# Sheet4.net
KiCad netlist of a schematic drawn in Altium Designer
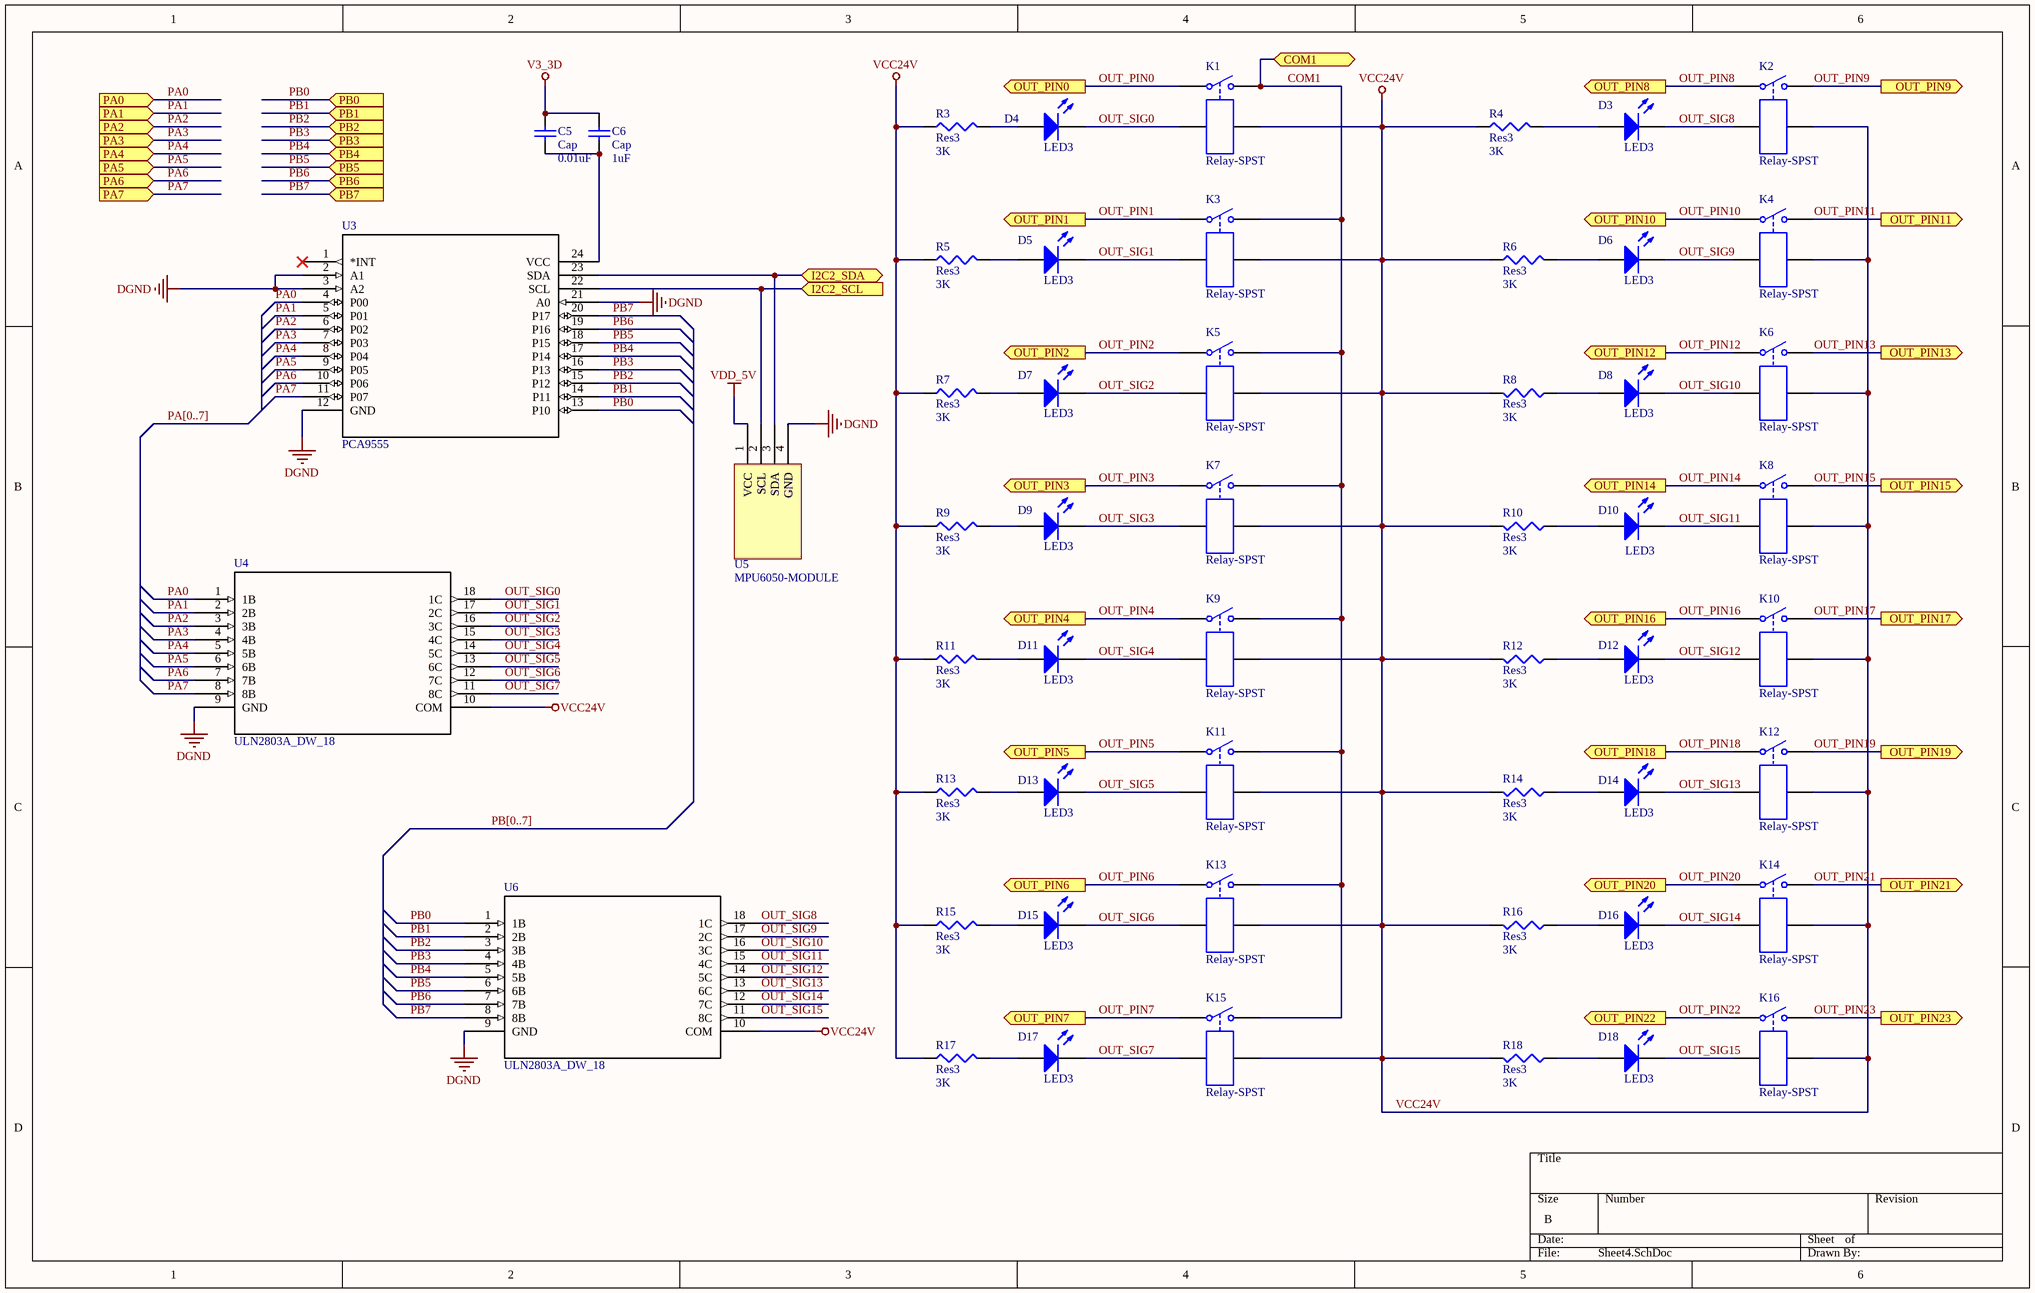
[diagram p0: Sheet4.SchDoc]

(export (version "E")
  (design (tool "Eeschema 10.0.6"))
  (components
    (comp (ref "C5")
      (value "Cap")
      (footprint "0805_cap")
      (description "Capacitor")
      (fields (field (name "ALTIUM_VALUE") "0.01uF") (field (name "PUBLISHER") "Altium Limited"))
      (libsource (lib "Miscellaneous Devices") (part "Cap"))
    )
    (comp (ref "C6")
      (value "Cap")
      (footprint "0805_cap")
      (description "Capacitor")
      (fields (field (name "ALTIUM_VALUE") "1uF") (field (name "PUBLISHER") "Altium Limited"))
      (libsource (lib "Miscellaneous Devices") (part "Cap"))
    )
    (comp (ref "D3")
      (value "LED3")
      (footprint "0805LED")
      (description "Typical BLUE SiC LED")
      (fields (field (name "PUBLISHER") "Altium Limited"))
      (libsource (lib "Miscellaneous Devices") (part "LED3"))
    )
    (comp (ref "D4")
      (value "LED3")
      (footprint "0805LED")
      (description "Typical BLUE SiC LED")
      (fields (field (name "PUBLISHER") "Altium Limited"))
      (libsource (lib "Miscellaneous Devices") (part "LED3"))
    )
    (comp (ref "D5")
      (value "LED3")
      (footprint "0805LED")
      (description "Typical BLUE SiC LED")
      (fields (field (name "PUBLISHER") "Altium Limited"))
      (libsource (lib "Miscellaneous Devices") (part "LED3"))
    )
    (comp (ref "D6")
      (value "LED3")
      (footprint "0805LED")
      (description "Typical BLUE SiC LED")
      (fields (field (name "PUBLISHER") "Altium Limited"))
      (libsource (lib "Miscellaneous Devices") (part "LED3"))
    )
    (comp (ref "D7")
      (value "LED3")
      (footprint "0805LED")
      (description "Typical BLUE SiC LED")
      (fields (field (name "PUBLISHER") "Altium Limited"))
      (libsource (lib "Miscellaneous Devices") (part "LED3"))
    )
    (comp (ref "D8")
      (value "LED3")
      (footprint "0805LED")
      (description "Typical BLUE SiC LED")
      (fields (field (name "PUBLISHER") "Altium Limited"))
      (libsource (lib "Miscellaneous Devices") (part "LED3"))
    )
    (comp (ref "D9")
      (value "LED3")
      (footprint "0805LED")
      (description "Typical BLUE SiC LED")
      (fields (field (name "PUBLISHER") "Altium Limited"))
      (libsource (lib "Miscellaneous Devices") (part "LED3"))
    )
    (comp (ref "D10")
      (value "LED3")
      (footprint "0805LED")
      (description "Typical BLUE SiC LED")
      (fields (field (name "PUBLISHER") "Altium Limited"))
      (libsource (lib "Miscellaneous Devices") (part "LED3"))
    )
    (comp (ref "D11")
      (value "LED3")
      (footprint "0805LED")
      (description "Typical BLUE SiC LED")
      (fields (field (name "PUBLISHER") "Altium Limited"))
      (libsource (lib "Miscellaneous Devices") (part "LED3"))
    )
    (comp (ref "D12")
      (value "LED3")
      (footprint "0805LED")
      (description "Typical BLUE SiC LED")
      (fields (field (name "PUBLISHER") "Altium Limited"))
      (libsource (lib "Miscellaneous Devices") (part "LED3"))
    )
    (comp (ref "D13")
      (value "LED3")
      (footprint "0805LED")
      (description "Typical BLUE SiC LED")
      (fields (field (name "PUBLISHER") "Altium Limited"))
      (libsource (lib "Miscellaneous Devices") (part "LED3"))
    )
    (comp (ref "D14")
      (value "LED3")
      (footprint "0805LED")
      (description "Typical BLUE SiC LED")
      (fields (field (name "PUBLISHER") "Altium Limited"))
      (libsource (lib "Miscellaneous Devices") (part "LED3"))
    )
    (comp (ref "D15")
      (value "LED3")
      (footprint "0805LED")
      (description "Typical BLUE SiC LED")
      (fields (field (name "PUBLISHER") "Altium Limited"))
      (libsource (lib "Miscellaneous Devices") (part "LED3"))
    )
    (comp (ref "D16")
      (value "LED3")
      (footprint "0805LED")
      (description "Typical BLUE SiC LED")
      (fields (field (name "PUBLISHER") "Altium Limited"))
      (libsource (lib "Miscellaneous Devices") (part "LED3"))
    )
    (comp (ref "D17")
      (value "LED3")
      (footprint "0805LED")
      (description "Typical BLUE SiC LED")
      (fields (field (name "PUBLISHER") "Altium Limited"))
      (libsource (lib "Miscellaneous Devices") (part "LED3"))
    )
    (comp (ref "D18")
      (value "LED3")
      (footprint "0805LED")
      (description "Typical BLUE SiC LED")
      (fields (field (name "PUBLISHER") "Altium Limited"))
      (libsource (lib "Miscellaneous Devices") (part "LED3"))
    )
    (comp (ref "K1")
      (value "Relay-SPST")
      (footprint "PA1a-24v")
      (description "Single-Pole Single-Throw Relay")
      (fields (field (name "PUBLISHER") "Altium Limited"))
      (libsource (lib "Miscellaneous Devices") (part "Relay-SPST"))
    )
    (comp (ref "K2")
      (value "Relay-SPST")
      (footprint "PA1a-24v")
      (description "Single-Pole Single-Throw Relay")
      (fields (field (name "PUBLISHER") "Altium Limited"))
      (libsource (lib "Miscellaneous Devices") (part "Relay-SPST"))
    )
    (comp (ref "K3")
      (value "Relay-SPST")
      (footprint "PA1a-24v")
      (description "Single-Pole Single-Throw Relay")
      (fields (field (name "PUBLISHER") "Altium Limited"))
      (libsource (lib "Miscellaneous Devices") (part "Relay-SPST"))
    )
    (comp (ref "K4")
      (value "Relay-SPST")
      (footprint "PA1a-24v")
      (description "Single-Pole Single-Throw Relay")
      (fields (field (name "PUBLISHER") "Altium Limited"))
      (libsource (lib "Miscellaneous Devices") (part "Relay-SPST"))
    )
    (comp (ref "K5")
      (value "Relay-SPST")
      (footprint "PA1a-24v")
      (description "Single-Pole Single-Throw Relay")
      (fields (field (name "PUBLISHER") "Altium Limited"))
      (libsource (lib "Miscellaneous Devices") (part "Relay-SPST"))
    )
    (comp (ref "K6")
      (value "Relay-SPST")
      (footprint "PA1a-24v")
      (description "Single-Pole Single-Throw Relay")
      (fields (field (name "PUBLISHER") "Altium Limited"))
      (libsource (lib "Miscellaneous Devices") (part "Relay-SPST"))
    )
    (comp (ref "K7")
      (value "Relay-SPST")
      (footprint "PA1a-24v")
      (description "Single-Pole Single-Throw Relay")
      (fields (field (name "PUBLISHER") "Altium Limited"))
      (libsource (lib "Miscellaneous Devices") (part "Relay-SPST"))
    )
    (comp (ref "K8")
      (value "Relay-SPST")
      (footprint "PA1a-24v")
      (description "Single-Pole Single-Throw Relay")
      (fields (field (name "PUBLISHER") "Altium Limited"))
      (libsource (lib "Miscellaneous Devices") (part "Relay-SPST"))
    )
    (comp (ref "K9")
      (value "Relay-SPST")
      (footprint "PA1a-24v")
      (description "Single-Pole Single-Throw Relay")
      (fields (field (name "PUBLISHER") "Altium Limited"))
      (libsource (lib "Miscellaneous Devices") (part "Relay-SPST"))
    )
    (comp (ref "K10")
      (value "Relay-SPST")
      (footprint "PA1a-24v")
      (description "Single-Pole Single-Throw Relay")
      (fields (field (name "PUBLISHER") "Altium Limited"))
      (libsource (lib "Miscellaneous Devices") (part "Relay-SPST"))
    )
    (comp (ref "K11")
      (value "Relay-SPST")
      (footprint "PA1a-24v")
      (description "Single-Pole Single-Throw Relay")
      (fields (field (name "PUBLISHER") "Altium Limited"))
      (libsource (lib "Miscellaneous Devices") (part "Relay-SPST"))
    )
    (comp (ref "K12")
      (value "Relay-SPST")
      (footprint "PA1a-24v")
      (description "Single-Pole Single-Throw Relay")
      (fields (field (name "PUBLISHER") "Altium Limited"))
      (libsource (lib "Miscellaneous Devices") (part "Relay-SPST"))
    )
    (comp (ref "K13")
      (value "Relay-SPST")
      (footprint "PA1a-24v")
      (description "Single-Pole Single-Throw Relay")
      (fields (field (name "PUBLISHER") "Altium Limited"))
      (libsource (lib "Miscellaneous Devices") (part "Relay-SPST"))
    )
    (comp (ref "K14")
      (value "Relay-SPST")
      (footprint "PA1a-24v")
      (description "Single-Pole Single-Throw Relay")
      (fields (field (name "PUBLISHER") "Altium Limited"))
      (libsource (lib "Miscellaneous Devices") (part "Relay-SPST"))
    )
    (comp (ref "K15")
      (value "Relay-SPST")
      (footprint "PA1a-24v")
      (description "Single-Pole Single-Throw Relay")
      (fields (field (name "PUBLISHER") "Altium Limited"))
      (libsource (lib "Miscellaneous Devices") (part "Relay-SPST"))
    )
    (comp (ref "K16")
      (value "Relay-SPST")
      (footprint "PA1a-24v")
      (description "Single-Pole Single-Throw Relay")
      (fields (field (name "PUBLISHER") "Altium Limited"))
      (libsource (lib "Miscellaneous Devices") (part "Relay-SPST"))
    )
    (comp (ref "R3")
      (value "Res3")
      (footprint "0805")
      (description "Resistor")
      (fields (field (name "ALTIUM_VALUE") "3K") (field (name "PUBLISHER") "Altium Limited"))
      (libsource (lib "Miscellaneous Devices") (part "Res3"))
    )
    (comp (ref "R4")
      (value "Res3")
      (footprint "0805")
      (description "Resistor")
      (fields (field (name "ALTIUM_VALUE") "3K") (field (name "PUBLISHER") "Altium Limited"))
      (libsource (lib "Miscellaneous Devices") (part "Res3"))
    )
    (comp (ref "R5")
      (value "Res3")
      (footprint "0805")
      (description "Resistor")
      (fields (field (name "ALTIUM_VALUE") "3K") (field (name "PUBLISHER") "Altium Limited"))
      (libsource (lib "Miscellaneous Devices") (part "Res3"))
    )
    (comp (ref "R6")
      (value "Res3")
      (footprint "0805")
      (description "Resistor")
      (fields (field (name "ALTIUM_VALUE") "3K") (field (name "PUBLISHER") "Altium Limited"))
      (libsource (lib "Miscellaneous Devices") (part "Res3"))
    )
    (comp (ref "R7")
      (value "Res3")
      (footprint "0805")
      (description "Resistor")
      (fields (field (name "ALTIUM_VALUE") "3K") (field (name "PUBLISHER") "Altium Limited"))
      (libsource (lib "Miscellaneous Devices") (part "Res3"))
    )
    (comp (ref "R8")
      (value "Res3")
      (footprint "0805")
      (description "Resistor")
      (fields (field (name "ALTIUM_VALUE") "3K") (field (name "PUBLISHER") "Altium Limited"))
      (libsource (lib "Miscellaneous Devices") (part "Res3"))
    )
    (comp (ref "R9")
      (value "Res3")
      (footprint "0805")
      (description "Resistor")
      (fields (field (name "ALTIUM_VALUE") "3K") (field (name "PUBLISHER") "Altium Limited"))
      (libsource (lib "Miscellaneous Devices") (part "Res3"))
    )
    (comp (ref "R10")
      (value "Res3")
      (footprint "0805")
      (description "Resistor")
      (fields (field (name "ALTIUM_VALUE") "3K") (field (name "PUBLISHER") "Altium Limited"))
      (libsource (lib "Miscellaneous Devices") (part "Res3"))
    )
    (comp (ref "R11")
      (value "Res3")
      (footprint "0805")
      (description "Resistor")
      (fields (field (name "ALTIUM_VALUE") "3K") (field (name "PUBLISHER") "Altium Limited"))
      (libsource (lib "Miscellaneous Devices") (part "Res3"))
    )
    (comp (ref "R12")
      (value "Res3")
      (footprint "0805")
      (description "Resistor")
      (fields (field (name "ALTIUM_VALUE") "3K") (field (name "PUBLISHER") "Altium Limited"))
      (libsource (lib "Miscellaneous Devices") (part "Res3"))
    )
    (comp (ref "R13")
      (value "Res3")
      (footprint "0805")
      (description "Resistor")
      (fields (field (name "ALTIUM_VALUE") "3K") (field (name "PUBLISHER") "Altium Limited"))
      (libsource (lib "Miscellaneous Devices") (part "Res3"))
    )
    (comp (ref "R14")
      (value "Res3")
      (footprint "0805")
      (description "Resistor")
      (fields (field (name "ALTIUM_VALUE") "3K") (field (name "PUBLISHER") "Altium Limited"))
      (libsource (lib "Miscellaneous Devices") (part "Res3"))
    )
    (comp (ref "R15")
      (value "Res3")
      (footprint "0805")
      (description "Resistor")
      (fields (field (name "ALTIUM_VALUE") "3K") (field (name "PUBLISHER") "Altium Limited"))
      (libsource (lib "Miscellaneous Devices") (part "Res3"))
    )
    (comp (ref "R16")
      (value "Res3")
      (footprint "0805")
      (description "Resistor")
      (fields (field (name "ALTIUM_VALUE") "3K") (field (name "PUBLISHER") "Altium Limited"))
      (libsource (lib "Miscellaneous Devices") (part "Res3"))
    )
    (comp (ref "R17")
      (value "Res3")
      (footprint "0805")
      (description "Resistor")
      (fields (field (name "ALTIUM_VALUE") "3K") (field (name "PUBLISHER") "Altium Limited"))
      (libsource (lib "Miscellaneous Devices") (part "Res3"))
    )
    (comp (ref "R18")
      (value "Res3")
      (footprint "0805")
      (description "Resistor")
      (fields (field (name "ALTIUM_VALUE") "3K") (field (name "PUBLISHER") "Altium Limited"))
      (libsource (lib "Miscellaneous Devices") (part "Res3"))
    )
    (comp (ref "U3")
      (value "PCA9555")
      (footprint "PW24")
      (description "Imported")
      (fields
        (field (name "MANUFACTURER") "Texas Instruments")
        (field (name "GENERIC_PART_NUMBER") "PCF8575")
      )
      (libsource (lib "dolphi_ecs") (part "PCF8575_PW_24"))
    )
    (comp (ref "U4")
      (value "ULN2803A_DW_18")
      (footprint "DW18")
      (description "Imported")
      (fields
        (field (name "MANUFACTURER") "Texas Instruments")
        (field (name "GENERIC_PART_NUMBER") "ULN2803A")
      )
      (libsource (lib "dolphi_ecs") (part "ULN2803A_DW_18"))
    )
    (comp (ref "U5")
      (value "MPU6050-MODULE")
      (footprint "MPU6050-MODULE")
      (libsource (lib "dolphi_ecs") (part "MPU6050-MODULE"))
    )
    (comp (ref "U6")
      (value "ULN2803A_DW_18")
      (footprint "DW18")
      (description "Imported")
      (fields
        (field (name "MANUFACTURER") "Texas Instruments")
        (field (name "GENERIC_PART_NUMBER") "ULN2803A")
      )
      (libsource (lib "dolphi_ecs") (part "ULN2803A_DW_18"))
    )
  )
  (nets
    (net (code "1") (name "/COM1") (class "Default")
      (node (ref "K1") (pin "2") (pinfunction "2_2") (pintype "passive"))
      (node (ref "K11") (pin "2") (pinfunction "2_2") (pintype "passive"))
      (node (ref "K13") (pin "2") (pinfunction "2_2") (pintype "passive"))
      (node (ref "K15") (pin "2") (pinfunction "2_2") (pintype "passive"))
      (node (ref "K3") (pin "2") (pinfunction "2_2") (pintype "passive"))
      (node (ref "K5") (pin "2") (pinfunction "2_2") (pintype "passive"))
      (node (ref "K7") (pin "2") (pinfunction "2_2") (pintype "passive"))
      (node (ref "K9") (pin "2") (pinfunction "2_2") (pintype "passive"))
    )
    (net (code "2") (name "/I2C2_SCL") (class "Default")
      (node (ref "U3") (pin "22") (pinfunction "SCL_22") (pintype "passive"))
      (node (ref "U5") (pin "2") (pinfunction "SCL_2") (pintype "passive"))
    )
    (net (code "3") (name "/I2C2_SDA") (class "Default")
      (node (ref "U3") (pin "23") (pinfunction "SDA_23") (pintype "passive"))
      (node (ref "U5") (pin "3") (pinfunction "SDA_3") (pintype "passive"))
    )
    (net (code "4") (name "/OUT_PIN0") (class "Default")
      (node (ref "K1") (pin "1") (pinfunction "1_1") (pintype "passive"))
    )
    (net (code "5") (name "/OUT_PIN1") (class "Default")
      (node (ref "K3") (pin "1") (pinfunction "1_1") (pintype "passive"))
    )
    (net (code "6") (name "/OUT_PIN2") (class "Default")
      (node (ref "K5") (pin "1") (pinfunction "1_1") (pintype "passive"))
    )
    (net (code "7") (name "/OUT_PIN3") (class "Default")
      (node (ref "K7") (pin "1") (pinfunction "1_1") (pintype "passive"))
    )
    (net (code "8") (name "/OUT_PIN4") (class "Default")
      (node (ref "K9") (pin "1") (pinfunction "1_1") (pintype "passive"))
    )
    (net (code "9") (name "/OUT_PIN5") (class "Default")
      (node (ref "K11") (pin "1") (pinfunction "1_1") (pintype "passive"))
    )
    (net (code "10") (name "/OUT_PIN6") (class "Default")
      (node (ref "K13") (pin "1") (pinfunction "1_1") (pintype "passive"))
    )
    (net (code "11") (name "/OUT_PIN7") (class "Default")
      (node (ref "K15") (pin "1") (pinfunction "1_1") (pintype "passive"))
    )
    (net (code "12") (name "/OUT_PIN8") (class "Default")
      (node (ref "K2") (pin "1") (pinfunction "1_1") (pintype "passive"))
    )
    (net (code "13") (name "/OUT_PIN9") (class "Default")
      (node (ref "K2") (pin "2") (pinfunction "2_2") (pintype "passive"))
    )
    (net (code "14") (name "/OUT_PIN10") (class "Default")
      (node (ref "K4") (pin "1") (pinfunction "1_1") (pintype "passive"))
    )
    (net (code "15") (name "/OUT_PIN11") (class "Default")
      (node (ref "K4") (pin "2") (pinfunction "2_2") (pintype "passive"))
    )
    (net (code "16") (name "/OUT_PIN12") (class "Default")
      (node (ref "K6") (pin "1") (pinfunction "1_1") (pintype "passive"))
    )
    (net (code "17") (name "/OUT_PIN13") (class "Default")
      (node (ref "K6") (pin "2") (pinfunction "2_2") (pintype "passive"))
    )
    (net (code "18") (name "/OUT_PIN14") (class "Default")
      (node (ref "K8") (pin "1") (pinfunction "1_1") (pintype "passive"))
    )
    (net (code "19") (name "/OUT_PIN15") (class "Default")
      (node (ref "K8") (pin "2") (pinfunction "2_2") (pintype "passive"))
    )
    (net (code "20") (name "/OUT_PIN16") (class "Default")
      (node (ref "K10") (pin "1") (pinfunction "1_1") (pintype "passive"))
    )
    (net (code "21") (name "/OUT_PIN17") (class "Default")
      (node (ref "K10") (pin "2") (pinfunction "2_2") (pintype "passive"))
    )
    (net (code "22") (name "/OUT_PIN18") (class "Default")
      (node (ref "K12") (pin "1") (pinfunction "1_1") (pintype "passive"))
    )
    (net (code "23") (name "/OUT_PIN19") (class "Default")
      (node (ref "K12") (pin "2") (pinfunction "2_2") (pintype "passive"))
    )
    (net (code "24") (name "/OUT_PIN20") (class "Default")
      (node (ref "K14") (pin "1") (pinfunction "1_1") (pintype "passive"))
    )
    (net (code "25") (name "/OUT_PIN21") (class "Default")
      (node (ref "K14") (pin "2") (pinfunction "2_2") (pintype "passive"))
    )
    (net (code "26") (name "/OUT_PIN22") (class "Default")
      (node (ref "K16") (pin "1") (pinfunction "1_1") (pintype "passive"))
    )
    (net (code "27") (name "/OUT_PIN23") (class "Default")
      (node (ref "K16") (pin "2") (pinfunction "2_2") (pintype "passive"))
    )
    (net (code "28") (name "/OUT_SIG0") (class "Default")
      (node (ref "D4") (pin "2") (pinfunction "K_2") (pintype "passive"))
      (node (ref "K1") (pin "3") (pinfunction "3_3") (pintype "passive"))
      (node (ref "U4") (pin "18") (pinfunction "1C_18") (pintype "output"))
    )
    (net (code "29") (name "/OUT_SIG1") (class "Default")
      (node (ref "D5") (pin "2") (pinfunction "K_2") (pintype "passive"))
      (node (ref "K3") (pin "3") (pinfunction "3_3") (pintype "passive"))
      (node (ref "U4") (pin "17") (pinfunction "2C_17") (pintype "output"))
    )
    (net (code "30") (name "/OUT_SIG2") (class "Default")
      (node (ref "D7") (pin "2") (pinfunction "K_2") (pintype "passive"))
      (node (ref "K5") (pin "3") (pinfunction "3_3") (pintype "passive"))
      (node (ref "U4") (pin "16") (pinfunction "3C_16") (pintype "output"))
    )
    (net (code "31") (name "/OUT_SIG3") (class "Default")
      (node (ref "D9") (pin "2") (pinfunction "K_2") (pintype "passive"))
      (node (ref "K7") (pin "3") (pinfunction "3_3") (pintype "passive"))
      (node (ref "U4") (pin "15") (pinfunction "4C_15") (pintype "output"))
    )
    (net (code "32") (name "/OUT_SIG4") (class "Default")
      (node (ref "D11") (pin "2") (pinfunction "K_2") (pintype "passive"))
      (node (ref "K9") (pin "3") (pinfunction "3_3") (pintype "passive"))
      (node (ref "U4") (pin "14") (pinfunction "5C_14") (pintype "output"))
    )
    (net (code "33") (name "/OUT_SIG5") (class "Default")
      (node (ref "D13") (pin "2") (pinfunction "K_2") (pintype "passive"))
      (node (ref "K11") (pin "3") (pinfunction "3_3") (pintype "passive"))
      (node (ref "U4") (pin "13") (pinfunction "6C_13") (pintype "output"))
    )
    (net (code "34") (name "/OUT_SIG6") (class "Default")
      (node (ref "D15") (pin "2") (pinfunction "K_2") (pintype "passive"))
      (node (ref "K13") (pin "3") (pinfunction "3_3") (pintype "passive"))
      (node (ref "U4") (pin "12") (pinfunction "7C_12") (pintype "output"))
    )
    (net (code "35") (name "/OUT_SIG7") (class "Default")
      (node (ref "D17") (pin "2") (pinfunction "K_2") (pintype "passive"))
      (node (ref "K15") (pin "3") (pinfunction "3_3") (pintype "passive"))
      (node (ref "U4") (pin "11") (pinfunction "8C_11") (pintype "output"))
    )
    (net (code "36") (name "/OUT_SIG8") (class "Default")
      (node (ref "D3") (pin "2") (pinfunction "K_2") (pintype "passive"))
      (node (ref "K2") (pin "3") (pinfunction "3_3") (pintype "passive"))
      (node (ref "U6") (pin "18") (pinfunction "1C_18") (pintype "output"))
    )
    (net (code "37") (name "/OUT_SIG9") (class "Default")
      (node (ref "D6") (pin "2") (pinfunction "K_2") (pintype "passive"))
      (node (ref "K4") (pin "3") (pinfunction "3_3") (pintype "passive"))
      (node (ref "U6") (pin "17") (pinfunction "2C_17") (pintype "output"))
    )
    (net (code "38") (name "/OUT_SIG10") (class "Default")
      (node (ref "D8") (pin "2") (pinfunction "K_2") (pintype "passive"))
      (node (ref "K6") (pin "3") (pinfunction "3_3") (pintype "passive"))
      (node (ref "U6") (pin "16") (pinfunction "3C_16") (pintype "output"))
    )
    (net (code "39") (name "/OUT_SIG11") (class "Default")
      (node (ref "D10") (pin "2") (pinfunction "K_2") (pintype "passive"))
      (node (ref "K8") (pin "3") (pinfunction "3_3") (pintype "passive"))
      (node (ref "U6") (pin "15") (pinfunction "4C_15") (pintype "output"))
    )
    (net (code "40") (name "/OUT_SIG12") (class "Default")
      (node (ref "D12") (pin "2") (pinfunction "K_2") (pintype "passive"))
      (node (ref "K10") (pin "3") (pinfunction "3_3") (pintype "passive"))
      (node (ref "U6") (pin "14") (pinfunction "5C_14") (pintype "output"))
    )
    (net (code "41") (name "/OUT_SIG13") (class "Default")
      (node (ref "D14") (pin "2") (pinfunction "K_2") (pintype "passive"))
      (node (ref "K12") (pin "3") (pinfunction "3_3") (pintype "passive"))
      (node (ref "U6") (pin "13") (pinfunction "6C_13") (pintype "output"))
    )
    (net (code "42") (name "/OUT_SIG14") (class "Default")
      (node (ref "D16") (pin "2") (pinfunction "K_2") (pintype "passive"))
      (node (ref "K14") (pin "3") (pinfunction "3_3") (pintype "passive"))
      (node (ref "U6") (pin "12") (pinfunction "7C_12") (pintype "output"))
    )
    (net (code "43") (name "/OUT_SIG15") (class "Default")
      (node (ref "D18") (pin "2") (pinfunction "K_2") (pintype "passive"))
      (node (ref "K16") (pin "3") (pinfunction "3_3") (pintype "passive"))
      (node (ref "U6") (pin "11") (pinfunction "8C_11") (pintype "output"))
    )
    (net (code "44") (name "/PA0") (class "Default")
      (node (ref "U3") (pin "4") (pinfunction "P00_4") (pintype "bidirectional"))
      (node (ref "U4") (pin "1") (pinfunction "1B_1") (pintype "input"))
    )
    (net (code "45") (name "/PA1") (class "Default")
      (node (ref "U3") (pin "5") (pinfunction "P01_5") (pintype "bidirectional"))
      (node (ref "U4") (pin "2") (pinfunction "2B_2") (pintype "input"))
    )
    (net (code "46") (name "/PA2") (class "Default")
      (node (ref "U3") (pin "6") (pinfunction "P02_6") (pintype "bidirectional"))
      (node (ref "U4") (pin "3") (pinfunction "3B_3") (pintype "input"))
    )
    (net (code "47") (name "/PA3") (class "Default")
      (node (ref "U3") (pin "7") (pinfunction "P03_7") (pintype "bidirectional"))
      (node (ref "U4") (pin "4") (pinfunction "4B_4") (pintype "input"))
    )
    (net (code "48") (name "/PA4") (class "Default")
      (node (ref "U3") (pin "8") (pinfunction "P04_8") (pintype "bidirectional"))
      (node (ref "U4") (pin "5") (pinfunction "5B_5") (pintype "input"))
    )
    (net (code "49") (name "/PA5") (class "Default")
      (node (ref "U3") (pin "9") (pinfunction "P05_9") (pintype "bidirectional"))
      (node (ref "U4") (pin "6") (pinfunction "6B_6") (pintype "input"))
    )
    (net (code "50") (name "/PA6") (class "Default")
      (node (ref "U3") (pin "10") (pinfunction "P06_10") (pintype "bidirectional"))
      (node (ref "U4") (pin "7") (pinfunction "7B_7") (pintype "input"))
    )
    (net (code "51") (name "/PA7") (class "Default")
      (node (ref "U3") (pin "11") (pinfunction "P07_11") (pintype "bidirectional"))
      (node (ref "U4") (pin "8") (pinfunction "8B_8") (pintype "input"))
    )
    (net (code "53") (name "/PB0") (class "Default")
      (node (ref "U3") (pin "13") (pinfunction "P10_13") (pintype "bidirectional"))
      (node (ref "U6") (pin "1") (pinfunction "1B_1") (pintype "input"))
    )
    (net (code "54") (name "/PB1") (class "Default")
      (node (ref "U3") (pin "14") (pinfunction "P11_14") (pintype "bidirectional"))
      (node (ref "U6") (pin "2") (pinfunction "2B_2") (pintype "input"))
    )
    (net (code "55") (name "/PB2") (class "Default")
      (node (ref "U3") (pin "15") (pinfunction "P12_15") (pintype "bidirectional"))
      (node (ref "U6") (pin "3") (pinfunction "3B_3") (pintype "input"))
    )
    (net (code "56") (name "/PB3") (class "Default")
      (node (ref "U3") (pin "16") (pinfunction "P13_16") (pintype "bidirectional"))
      (node (ref "U6") (pin "4") (pinfunction "4B_4") (pintype "input"))
    )
    (net (code "57") (name "/PB4") (class "Default")
      (node (ref "U3") (pin "17") (pinfunction "P14_17") (pintype "bidirectional"))
      (node (ref "U6") (pin "5") (pinfunction "5B_5") (pintype "input"))
    )
    (net (code "58") (name "/PB5") (class "Default")
      (node (ref "U3") (pin "18") (pinfunction "P15_18") (pintype "bidirectional"))
      (node (ref "U6") (pin "6") (pinfunction "6B_6") (pintype "input"))
    )
    (net (code "59") (name "/PB6") (class "Default")
      (node (ref "U3") (pin "19") (pinfunction "P16_19") (pintype "bidirectional"))
      (node (ref "U6") (pin "7") (pinfunction "7B_7") (pintype "input"))
    )
    (net (code "60") (name "/PB7") (class "Default")
      (node (ref "U3") (pin "20") (pinfunction "P17_20") (pintype "bidirectional"))
      (node (ref "U6") (pin "8") (pinfunction "8B_8") (pintype "input"))
    )
    (net (code "62") (name "DGND") (class "Default")
      (node (ref "U3") (pin "12") (pinfunction "GND_12") (pintype "power_in"))
      (node (ref "U3") (pin "2") (pinfunction "A1_2") (pintype "input"))
      (node (ref "U3") (pin "21") (pinfunction "A0_21") (pintype "input"))
      (node (ref "U3") (pin "3") (pinfunction "A2_3") (pintype "input"))
      (node (ref "U4") (pin "9") (pinfunction "GND_9") (pintype "power_in"))
      (node (ref "U5") (pin "4") (pinfunction "GND_4") (pintype "passive"))
      (node (ref "U6") (pin "9") (pinfunction "GND_9") (pintype "power_in"))
    )
    (net (code "63") (name "Net-(D3-A)") (class "Default")
      (node (ref "D3") (pin "1") (pinfunction "A_1") (pintype "passive"))
      (node (ref "R4") (pin "2") (pinfunction "2_2") (pintype "passive"))
    )
    (net (code "64") (name "Net-(D4-A)") (class "Default")
      (node (ref "D4") (pin "1") (pinfunction "A_1") (pintype "passive"))
      (node (ref "R3") (pin "2") (pinfunction "2_2") (pintype "passive"))
    )
    (net (code "65") (name "Net-(D5-A)") (class "Default")
      (node (ref "D5") (pin "1") (pinfunction "A_1") (pintype "passive"))
      (node (ref "R5") (pin "2") (pinfunction "2_2") (pintype "passive"))
    )
    (net (code "66") (name "Net-(D6-A)") (class "Default")
      (node (ref "D6") (pin "1") (pinfunction "A_1") (pintype "passive"))
      (node (ref "R6") (pin "2") (pinfunction "2_2") (pintype "passive"))
    )
    (net (code "67") (name "Net-(D7-A)") (class "Default")
      (node (ref "D7") (pin "1") (pinfunction "A_1") (pintype "passive"))
      (node (ref "R7") (pin "2") (pinfunction "2_2") (pintype "passive"))
    )
    (net (code "68") (name "Net-(D8-A)") (class "Default")
      (node (ref "D8") (pin "1") (pinfunction "A_1") (pintype "passive"))
      (node (ref "R8") (pin "1") (pinfunction "1_1") (pintype "passive"))
    )
    (net (code "69") (name "Net-(D9-A)") (class "Default")
      (node (ref "D9") (pin "1") (pinfunction "A_1") (pintype "passive"))
      (node (ref "R9") (pin "2") (pinfunction "2_2") (pintype "passive"))
    )
    (net (code "70") (name "Net-(D10-A)") (class "Default")
      (node (ref "D10") (pin "1") (pinfunction "A_1") (pintype "passive"))
      (node (ref "R10") (pin "1") (pinfunction "1_1") (pintype "passive"))
    )
    (net (code "71") (name "Net-(D11-A)") (class "Default")
      (node (ref "D11") (pin "1") (pinfunction "A_1") (pintype "passive"))
      (node (ref "R11") (pin "2") (pinfunction "2_2") (pintype "passive"))
    )
    (net (code "72") (name "Net-(D12-A)") (class "Default")
      (node (ref "D12") (pin "1") (pinfunction "A_1") (pintype "passive"))
      (node (ref "R12") (pin "1") (pinfunction "1_1") (pintype "passive"))
    )
    (net (code "73") (name "Net-(D13-A)") (class "Default")
      (node (ref "D13") (pin "1") (pinfunction "A_1") (pintype "passive"))
      (node (ref "R13") (pin "2") (pinfunction "2_2") (pintype "passive"))
    )
    (net (code "74") (name "Net-(D14-A)") (class "Default")
      (node (ref "D14") (pin "1") (pinfunction "A_1") (pintype "passive"))
      (node (ref "R14") (pin "1") (pinfunction "1_1") (pintype "passive"))
    )
    (net (code "75") (name "Net-(D15-A)") (class "Default")
      (node (ref "D15") (pin "1") (pinfunction "A_1") (pintype "passive"))
      (node (ref "R15") (pin "2") (pinfunction "2_2") (pintype "passive"))
    )
    (net (code "76") (name "Net-(D16-A)") (class "Default")
      (node (ref "D16") (pin "1") (pinfunction "A_1") (pintype "passive"))
      (node (ref "R16") (pin "1") (pinfunction "1_1") (pintype "passive"))
    )
    (net (code "77") (name "Net-(D17-A)") (class "Default")
      (node (ref "D17") (pin "1") (pinfunction "A_1") (pintype "passive"))
      (node (ref "R17") (pin "2") (pinfunction "2_2") (pintype "passive"))
    )
    (net (code "78") (name "Net-(D18-A)") (class "Default")
      (node (ref "D18") (pin "1") (pinfunction "A_1") (pintype "passive"))
      (node (ref "R18") (pin "1") (pinfunction "1_1") (pintype "passive"))
    )
    (net (code "79") (name "Net-(U3-VCC)") (class "Default")
      (node (ref "C5") (pin "1") (pinfunction "1_1") (pintype "passive"))
      (node (ref "C6") (pin "1") (pinfunction "1_1") (pintype "passive"))
      (node (ref "U3") (pin "24") (pinfunction "VCC_24") (pintype "power_in"))
    )
    (net (code "80") (name "V3_3D") (class "Default")
      (node (ref "C5") (pin "2") (pinfunction "2_2") (pintype "passive"))
      (node (ref "C6") (pin "2") (pinfunction "2_2") (pintype "passive"))
    )
    (net (code "81") (name "VCC24V") (class "Default")
      (node (ref "K1") (pin "4") (pinfunction "4_4") (pintype "passive"))
      (node (ref "K10") (pin "4") (pinfunction "4_4") (pintype "passive"))
      (node (ref "K11") (pin "4") (pinfunction "4_4") (pintype "passive"))
      (node (ref "K12") (pin "4") (pinfunction "4_4") (pintype "passive"))
      (node (ref "K13") (pin "4") (pinfunction "4_4") (pintype "passive"))
      (node (ref "K14") (pin "4") (pinfunction "4_4") (pintype "passive"))
      (node (ref "K15") (pin "4") (pinfunction "4_4") (pintype "passive"))
      (node (ref "K16") (pin "4") (pinfunction "4_4") (pintype "passive"))
      (node (ref "K2") (pin "4") (pinfunction "4_4") (pintype "passive"))
      (node (ref "K3") (pin "4") (pinfunction "4_4") (pintype "passive"))
      (node (ref "K4") (pin "4") (pinfunction "4_4") (pintype "passive"))
      (node (ref "K5") (pin "4") (pinfunction "4_4") (pintype "passive"))
      (node (ref "K6") (pin "4") (pinfunction "4_4") (pintype "passive"))
      (node (ref "K7") (pin "4") (pinfunction "4_4") (pintype "passive"))
      (node (ref "K8") (pin "4") (pinfunction "4_4") (pintype "passive"))
      (node (ref "K9") (pin "4") (pinfunction "4_4") (pintype "passive"))
      (node (ref "R10") (pin "2") (pinfunction "2_2") (pintype "passive"))
      (node (ref "R11") (pin "1") (pinfunction "1_1") (pintype "passive"))
      (node (ref "R12") (pin "2") (pinfunction "2_2") (pintype "passive"))
      (node (ref "R13") (pin "1") (pinfunction "1_1") (pintype "passive"))
      (node (ref "R14") (pin "2") (pinfunction "2_2") (pintype "passive"))
      (node (ref "R15") (pin "1") (pinfunction "1_1") (pintype "passive"))
      (node (ref "R16") (pin "2") (pinfunction "2_2") (pintype "passive"))
      (node (ref "R17") (pin "1") (pinfunction "1_1") (pintype "passive"))
      (node (ref "R18") (pin "2") (pinfunction "2_2") (pintype "passive"))
      (node (ref "R3") (pin "1") (pinfunction "1_1") (pintype "passive"))
      (node (ref "R4") (pin "1") (pinfunction "1_1") (pintype "passive"))
      (node (ref "R5") (pin "1") (pinfunction "1_1") (pintype "passive"))
      (node (ref "R6") (pin "1") (pinfunction "1_1") (pintype "passive"))
      (node (ref "R7") (pin "1") (pinfunction "1_1") (pintype "passive"))
      (node (ref "R8") (pin "2") (pinfunction "2_2") (pintype "passive"))
      (node (ref "R9") (pin "1") (pinfunction "1_1") (pintype "passive"))
      (node (ref "U4") (pin "10") (pinfunction "COM_10") (pintype "passive"))
      (node (ref "U6") (pin "10") (pinfunction "COM_10") (pintype "passive"))
    )
    (net (code "82") (name "VDD_5V") (class "Default")
      (node (ref "U5") (pin "1") (pinfunction "VCC_1") (pintype "passive"))
    )
    (net (code "83") (name "unconnected-(U3-*INT-Pad1)") (class "Default")
      (node (ref "U3") (pin "1") (pinfunction "*INT_1") (pintype "output+no_connect"))
    )
  )
)
